# Big_T_Split_-_ROM_Board.net
KiCad netlist of a schematic drawn in EAGLE
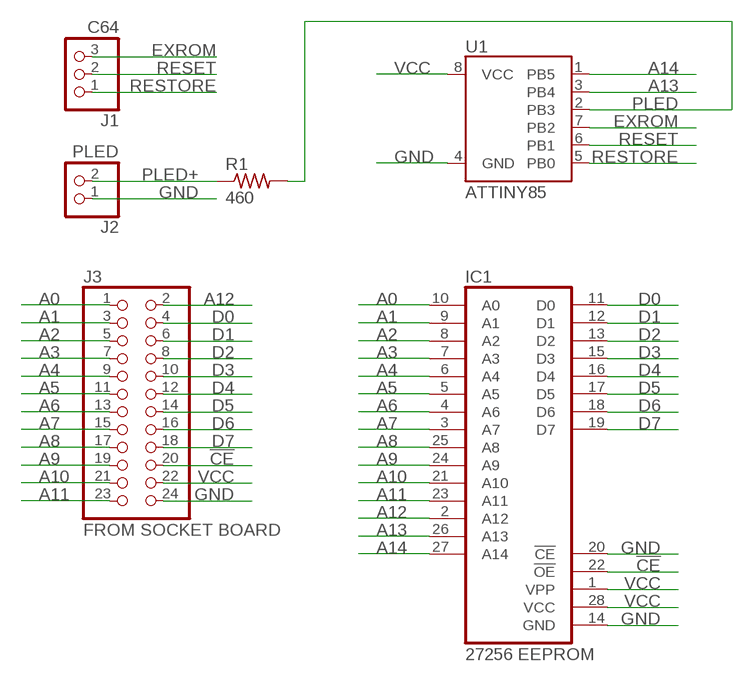
[diagram p0: schematic, sheet 1]

(export (version "E")
  (design (tool "Eeschema 10.0.6"))
  (components
    (comp (ref "IC1")
      (value "27256 EEPROM")
      (footprint "eagle-import:DIL28")
      (libsource (lib "eagle-import") (part "27256"))
    )
    (comp (ref "J1")
      (value "C64")
      (footprint "eagle-import:1X03")
      (libsource (lib "eagle-import") (part "PINHD-1X3"))
    )
    (comp (ref "J2")
      (value "PLED")
      (footprint "eagle-import:1X02")
      (libsource (lib "eagle-import") (part "PINHD-1X2"))
    )
    (comp (ref "J3")
      (value "FROM SOCKET BOARD")
      (footprint "eagle-import:2X12")
      (libsource (lib "eagle-import") (part "PINHD-2X12"))
    )
    (comp (ref "R1")
      (value "460")
      (footprint "eagle-import:R0805")
      (libsource (lib "eagle-import") (part "R-US_R0805"))
    )
    (comp (ref "U1")
      (value "ATTINY85")
      (footprint "eagle-import:ATTINY85")
      (libsource (lib "eagle-import") (part "ATTINY85"))
    )
  )
  (nets
    (net (code "1") (name "/A0") (class "Default")
      (node (ref "IC1") (pin "10") (pinfunction "A0_10") (pintype "bidirectional"))
      (node (ref "J3") (pin "1") (pinfunction "1_1") (pintype "passive"))
    )
    (net (code "2") (name "/A1") (class "Default")
      (node (ref "IC1") (pin "9") (pinfunction "A1_9") (pintype "bidirectional"))
      (node (ref "J3") (pin "3") (pinfunction "3_3") (pintype "passive"))
    )
    (net (code "3") (name "/A2") (class "Default")
      (node (ref "IC1") (pin "8") (pinfunction "A2_8") (pintype "bidirectional"))
      (node (ref "J3") (pin "5") (pinfunction "5_5") (pintype "passive"))
    )
    (net (code "4") (name "/A3") (class "Default")
      (node (ref "IC1") (pin "7") (pinfunction "A3_7") (pintype "bidirectional"))
      (node (ref "J3") (pin "7") (pinfunction "7_7") (pintype "passive"))
    )
    (net (code "5") (name "/A4") (class "Default")
      (node (ref "IC1") (pin "6") (pinfunction "A4_6") (pintype "bidirectional"))
      (node (ref "J3") (pin "9") (pinfunction "9_9") (pintype "passive"))
    )
    (net (code "6") (name "/A5") (class "Default")
      (node (ref "IC1") (pin "5") (pinfunction "A5_5") (pintype "bidirectional"))
      (node (ref "J3") (pin "11") (pinfunction "11_11") (pintype "passive"))
    )
    (net (code "7") (name "/A6") (class "Default")
      (node (ref "IC1") (pin "4") (pinfunction "A6_4") (pintype "bidirectional"))
      (node (ref "J3") (pin "13") (pinfunction "13_13") (pintype "passive"))
    )
    (net (code "8") (name "/A7") (class "Default")
      (node (ref "IC1") (pin "3") (pinfunction "A7_3") (pintype "bidirectional"))
      (node (ref "J3") (pin "15") (pinfunction "15_15") (pintype "passive"))
    )
    (net (code "9") (name "/A8") (class "Default")
      (node (ref "IC1") (pin "25") (pinfunction "A8_25") (pintype "bidirectional"))
      (node (ref "J3") (pin "17") (pinfunction "17_17") (pintype "passive"))
    )
    (net (code "10") (name "/A9") (class "Default")
      (node (ref "IC1") (pin "24") (pinfunction "A9_24") (pintype "bidirectional"))
      (node (ref "J3") (pin "19") (pinfunction "19_19") (pintype "passive"))
    )
    (net (code "11") (name "/A10") (class "Default")
      (node (ref "IC1") (pin "21") (pinfunction "A10_21") (pintype "bidirectional"))
      (node (ref "J3") (pin "21") (pinfunction "21_21") (pintype "passive"))
    )
    (net (code "12") (name "/A11") (class "Default")
      (node (ref "IC1") (pin "23") (pinfunction "A11_23") (pintype "bidirectional"))
      (node (ref "J3") (pin "23") (pinfunction "23_23") (pintype "passive"))
    )
    (net (code "13") (name "/A12") (class "Default")
      (node (ref "IC1") (pin "2") (pinfunction "A12_2") (pintype "bidirectional"))
      (node (ref "J3") (pin "2") (pinfunction "2_2") (pintype "passive"))
    )
    (net (code "14") (name "/A13") (class "Default")
      (node (ref "IC1") (pin "26") (pinfunction "A13_26") (pintype "bidirectional"))
      (node (ref "U1") (pin "3") (pinfunction "PB4_3") (pintype "bidirectional"))
    )
    (net (code "15") (name "/A14") (class "Default")
      (node (ref "IC1") (pin "27") (pinfunction "A14_27") (pintype "bidirectional"))
      (node (ref "U1") (pin "1") (pinfunction "PB5_1") (pintype "bidirectional"))
    )
    (net (code "16") (name "/D0") (class "Default")
      (node (ref "IC1") (pin "11") (pinfunction "D0_11") (pintype "bidirectional"))
      (node (ref "J3") (pin "4") (pinfunction "4_4") (pintype "passive"))
    )
    (net (code "17") (name "/D1") (class "Default")
      (node (ref "IC1") (pin "12") (pinfunction "D1_12") (pintype "bidirectional"))
      (node (ref "J3") (pin "6") (pinfunction "6_6") (pintype "passive"))
    )
    (net (code "18") (name "/D2") (class "Default")
      (node (ref "IC1") (pin "13") (pinfunction "D2_13") (pintype "bidirectional"))
      (node (ref "J3") (pin "8") (pinfunction "8_8") (pintype "passive"))
    )
    (net (code "19") (name "/D3") (class "Default")
      (node (ref "IC1") (pin "15") (pinfunction "D3_15") (pintype "bidirectional"))
      (node (ref "J3") (pin "10") (pinfunction "10_10") (pintype "passive"))
    )
    (net (code "20") (name "/D4") (class "Default")
      (node (ref "IC1") (pin "16") (pinfunction "D4_16") (pintype "bidirectional"))
      (node (ref "J3") (pin "12") (pinfunction "12_12") (pintype "passive"))
    )
    (net (code "21") (name "/D5") (class "Default")
      (node (ref "IC1") (pin "17") (pinfunction "D5_17") (pintype "bidirectional"))
      (node (ref "J3") (pin "14") (pinfunction "14_14") (pintype "passive"))
    )
    (net (code "22") (name "/D6") (class "Default")
      (node (ref "IC1") (pin "18") (pinfunction "D6_18") (pintype "bidirectional"))
      (node (ref "J3") (pin "16") (pinfunction "16_16") (pintype "passive"))
    )
    (net (code "23") (name "/D7") (class "Default")
      (node (ref "IC1") (pin "19") (pinfunction "D7_19") (pintype "bidirectional"))
      (node (ref "J3") (pin "18") (pinfunction "18_18") (pintype "passive"))
    )
    (net (code "24") (name "/EXROM") (class "Default")
      (node (ref "J1") (pin "3") (pinfunction "3_3") (pintype "passive"))
      (node (ref "U1") (pin "7") (pinfunction "PB2_7") (pintype "bidirectional"))
    )
    (net (code "25") (name "/GND") (class "Default")
      (node (ref "IC1") (pin "14") (pinfunction "GND_14") (pintype "power_in"))
      (node (ref "IC1") (pin "20") (pinfunction "~{CE}_20") (pintype "input"))
      (node (ref "J2") (pin "1") (pinfunction "1_1") (pintype "passive"))
      (node (ref "J3") (pin "24") (pinfunction "24_24") (pintype "passive"))
      (node (ref "U1") (pin "4") (pinfunction "GND_4") (pintype "bidirectional"))
    )
    (net (code "26") (name "/PLED") (class "Default")
      (node (ref "R1") (pin "2") (pinfunction "2_2") (pintype "passive"))
      (node (ref "U1") (pin "2") (pinfunction "PB3_2") (pintype "bidirectional"))
    )
    (net (code "27") (name "/PLED+") (class "Default")
      (node (ref "J2") (pin "2") (pinfunction "2_2") (pintype "passive"))
      (node (ref "R1") (pin "1") (pinfunction "1_1") (pintype "passive"))
    )
    (net (code "28") (name "/RESET") (class "Default")
      (node (ref "J1") (pin "2") (pinfunction "2_2") (pintype "passive"))
      (node (ref "U1") (pin "6") (pinfunction "PB1_6") (pintype "bidirectional"))
    )
    (net (code "29") (name "/RESTORE") (class "Default")
      (node (ref "J1") (pin "1") (pinfunction "1_1") (pintype "passive"))
      (node (ref "U1") (pin "5") (pinfunction "PB0_5") (pintype "bidirectional"))
    )
    (net (code "30") (name "/VCC") (class "Default")
      (node (ref "IC1") (pin "1") (pinfunction "VPP_1") (pintype "power_in"))
      (node (ref "IC1") (pin "28") (pinfunction "VCC_28") (pintype "power_in"))
      (node (ref "J3") (pin "22") (pinfunction "22_22") (pintype "passive"))
      (node (ref "U1") (pin "8") (pinfunction "VCC_8") (pintype "bidirectional"))
    )
    (net (code "31") (name "/~{CE}") (class "Default")
      (node (ref "IC1") (pin "22") (pinfunction "~{OE}_22") (pintype "output"))
      (node (ref "J3") (pin "20") (pinfunction "20_20") (pintype "passive"))
    )
  )
)
